# DRLVoltage.net
KiCad netlist of a schematic drawn in Altium Designer
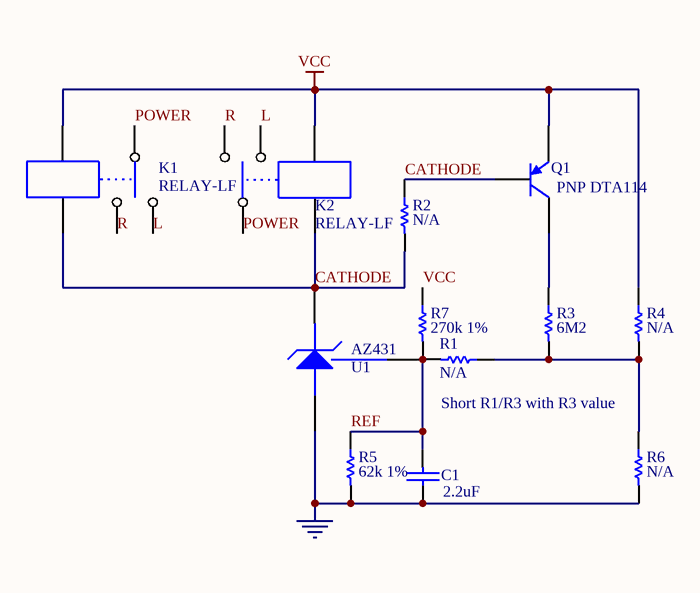
[diagram p0: DRLVoltage.SchDoc]

(export (version "E")
  (design (tool "Eeschema 10.0.6"))
  (components
    (comp (ref "C1")
      (value "2.2uF")
      (footprint "0603")
      (description "Capacitor")
      (libsource (lib "*") (part "CAP"))
    )
    (comp (ref "K1")
      (value "RELAY-LF")
      (footprint "RELAY5PIN")
      (libsource (lib "Miscellaneous Devices") (part "RELAY-SPDT"))
    )
    (comp (ref "K2")
      (value "RELAY-LF")
      (footprint "RELAY5PIN")
      (libsource (lib "Miscellaneous Devices") (part "RELAY-SPDT"))
    )
    (comp (ref "Q1")
      (value "PNP DTA114")
      (footprint "sot-23")
      (description "PNP Bipolar Transistor")
      (fields
        (field (name "MANUFACTURER") "Generic Components")
        (field (name "PUBLISHER") "Altium Hobart Technology Centre")
      )
      (libsource (lib "Miscellaneous Devices") (part "PNP"))
    )
    (comp (ref "R1")
      (value "N/A")
      (footprint "0603")
      (description "Resistor")
      (fields
        (field (name "MANUFACTURER") "Generic Components")
        (field (name "PUBLISHER") "Altium Hobart Technology Centre")
      )
      (libsource (lib "Miscellaneous Devices") (part "Res1"))
    )
    (comp (ref "R2")
      (value "N/A")
      (footprint "0603")
      (description "Resistor")
      (fields
        (field (name "MANUFACTURER") "Generic Components")
        (field (name "PUBLISHER") "Altium Hobart Technology Centre")
      )
      (libsource (lib "Miscellaneous Devices") (part "Res1"))
    )
    (comp (ref "R3")
      (value "6M2")
      (footprint "0603")
      (description "Resistor")
      (fields
        (field (name "MANUFACTURER") "Generic Components")
        (field (name "PUBLISHER") "Altium Hobart Technology Centre")
      )
      (libsource (lib "Miscellaneous Devices") (part "Res1"))
    )
    (comp (ref "R4")
      (value "N/A")
      (footprint "0603")
      (description "Resistor")
      (fields
        (field (name "MANUFACTURER") "Generic Components")
        (field (name "PUBLISHER") "Altium Hobart Technology Centre")
      )
      (libsource (lib "Miscellaneous Devices") (part "Res1"))
    )
    (comp (ref "R5")
      (value "62k 1%")
      (footprint "0603")
      (description "Resistor")
      (fields
        (field (name "MANUFACTURER") "Generic Components")
        (field (name "PUBLISHER") "Altium Hobart Technology Centre")
      )
      (libsource (lib "Miscellaneous Devices") (part "Res1"))
    )
    (comp (ref "R6")
      (value "N/A")
      (footprint "0603")
      (description "Resistor")
      (fields
        (field (name "MANUFACTURER") "Generic Components")
        (field (name "PUBLISHER") "Altium Hobart Technology Centre")
      )
      (libsource (lib "Miscellaneous Devices") (part "Res1"))
    )
    (comp (ref "R7")
      (value "270k 1%")
      (footprint "0603")
      (description "Resistor")
      (fields
        (field (name "MANUFACTURER") "Generic Components")
        (field (name "PUBLISHER") "Altium Hobart Technology Centre")
      )
      (libsource (lib "Miscellaneous Devices") (part "Res1"))
    )
    (comp (ref "U1") (value "AZ431") (footprint "SOT-23") (libsource (lib "Devices") (part "TL431")))
  )
  (nets
    (net (code "1") (name "/CATHODE") (class "Default")
      (node (ref "K1") (pin "5") (pinfunction "5_5") (pintype "passive"))
      (node (ref "K2") (pin "4") (pinfunction "4_4") (pintype "passive"))
      (node (ref "Q1") (pin "1") (pinfunction "B_1") (pintype "passive"))
      (node (ref "R2") (pin "1") (pinfunction "1_1") (pintype "passive"))
      (node (ref "R2") (pin "2") (pinfunction "2_2") (pintype "passive"))
      (node (ref "U1") (pin "3") (pinfunction "K_3") (pintype "passive"))
    )
    (net (code "2") (name "/L") (class "Default")
      (node (ref "K1") (pin "2") (pinfunction "2_2") (pintype "passive"))
      (node (ref "K2") (pin "3") (pinfunction "3_3") (pintype "passive"))
    )
    (net (code "3") (name "/POWER") (class "Default")
      (node (ref "K1") (pin "1") (pinfunction "1_1") (pintype "passive"))
      (node (ref "K2") (pin "1") (pinfunction "1_1") (pintype "passive"))
    )
    (net (code "4") (name "/R") (class "Default")
      (node (ref "K1") (pin "3") (pinfunction "3_3") (pintype "passive"))
      (node (ref "K2") (pin "2") (pinfunction "2_2") (pintype "passive"))
    )
    (net (code "5") (name "/REF") (class "Default")
      (node (ref "C1") (pin "1") (pinfunction "1_1") (pintype "passive"))
      (node (ref "R1") (pin "2") (pinfunction "2_2") (pintype "passive"))
      (node (ref "R5") (pin "1") (pinfunction "1_1") (pintype "passive"))
      (node (ref "R7") (pin "2") (pinfunction "2_2") (pintype "passive"))
      (node (ref "U1") (pin "1") (pinfunction "REF_1") (pintype "passive"))
    )
    (net (code "6") (name "Net-(Q1-C)") (class "Default")
      (node (ref "Q1") (pin "2") (pinfunction "C_2") (pintype "passive"))
      (node (ref "R3") (pin "1") (pinfunction "1_1") (pintype "passive"))
    )
    (net (code "7") (name "Net-(R1-Pad1)") (class "Default")
      (node (ref "R1") (pin "1") (pinfunction "1_1") (pintype "passive"))
      (node (ref "R3") (pin "2") (pinfunction "2_2") (pintype "passive"))
      (node (ref "R4") (pin "2") (pinfunction "2_2") (pintype "passive"))
      (node (ref "R6") (pin "1") (pinfunction "1_1") (pintype "passive"))
    )
    (net (code "8") (name "PGND") (class "Default")
      (node (ref "C1") (pin "2") (pinfunction "2_2") (pintype "passive"))
      (node (ref "R5") (pin "2") (pinfunction "2_2") (pintype "passive"))
      (node (ref "R6") (pin "2") (pinfunction "2_2") (pintype "passive"))
      (node (ref "U1") (pin "2") (pinfunction "A_2") (pintype "passive"))
    )
    (net (code "9") (name "VCC") (class "Default")
      (node (ref "K1") (pin "4") (pinfunction "4_4") (pintype "passive"))
      (node (ref "K2") (pin "5") (pinfunction "5_5") (pintype "passive"))
      (node (ref "Q1") (pin "3") (pinfunction "E_3") (pintype "passive"))
      (node (ref "R4") (pin "1") (pinfunction "1_1") (pintype "passive"))
      (node (ref "R7") (pin "1") (pinfunction "1_1") (pintype "passive"))
    )
  )
)
